# KammsensorV2.net
KiCad netlist of a schematic drawn in EAGLE
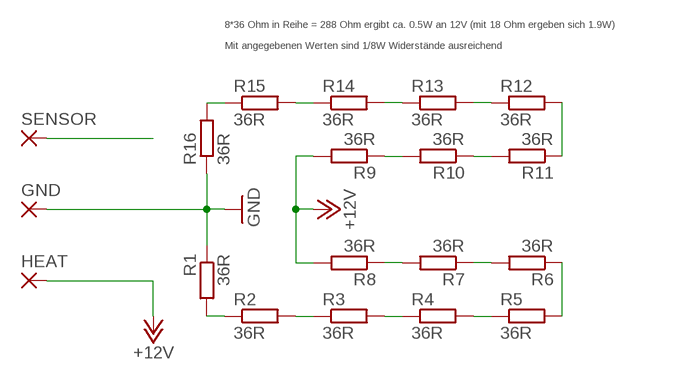
[diagram p0: schematic, sheet 1]

(export (version "E")
  (design (tool "Eeschema 10.0.6"))
  (components
    (comp (ref "GND")
      (value "WIREPADSMD5-1,8")
      (footprint "eagle-import:5-1,8")
      (libsource (lib "eagle-import") (part "WIREPADSMD5-1,8"))
    )
    (comp (ref "HEAT")
      (value "WIREPADSMD5-1,8")
      (footprint "eagle-import:5-1,8")
      (libsource (lib "eagle-import") (part "WIREPADSMD5-1,8"))
    )
    (comp (ref "R1")
      (value "36R")
      (footprint "eagle-import:M1206")
      (libsource (lib "eagle-import") (part "R-EU_M1206"))
    )
    (comp (ref "R2")
      (value "36R")
      (footprint "eagle-import:M1206")
      (libsource (lib "eagle-import") (part "R-EU_M1206"))
    )
    (comp (ref "R3")
      (value "36R")
      (footprint "eagle-import:M1206")
      (libsource (lib "eagle-import") (part "R-EU_M1206"))
    )
    (comp (ref "R4")
      (value "36R")
      (footprint "eagle-import:M1206")
      (libsource (lib "eagle-import") (part "R-EU_M1206"))
    )
    (comp (ref "R5")
      (value "36R")
      (footprint "eagle-import:M1206")
      (libsource (lib "eagle-import") (part "R-EU_M1206"))
    )
    (comp (ref "R6")
      (value "36R")
      (footprint "eagle-import:M1206")
      (libsource (lib "eagle-import") (part "R-EU_M1206"))
    )
    (comp (ref "R7")
      (value "36R")
      (footprint "eagle-import:M1206")
      (libsource (lib "eagle-import") (part "R-EU_M1206"))
    )
    (comp (ref "R8")
      (value "36R")
      (footprint "eagle-import:M1206")
      (libsource (lib "eagle-import") (part "R-EU_M1206"))
    )
    (comp (ref "R9")
      (value "36R")
      (footprint "eagle-import:M1206")
      (libsource (lib "eagle-import") (part "R-EU_M1206"))
    )
    (comp (ref "R10")
      (value "36R")
      (footprint "eagle-import:M1206")
      (libsource (lib "eagle-import") (part "R-EU_M1206"))
    )
    (comp (ref "R11")
      (value "36R")
      (footprint "eagle-import:M1206")
      (libsource (lib "eagle-import") (part "R-EU_M1206"))
    )
    (comp (ref "R12")
      (value "36R")
      (footprint "eagle-import:M1206")
      (libsource (lib "eagle-import") (part "R-EU_M1206"))
    )
    (comp (ref "R13")
      (value "36R")
      (footprint "eagle-import:M1206")
      (libsource (lib "eagle-import") (part "R-EU_M1206"))
    )
    (comp (ref "R14")
      (value "36R")
      (footprint "eagle-import:M1206")
      (libsource (lib "eagle-import") (part "R-EU_M1206"))
    )
    (comp (ref "R15")
      (value "36R")
      (footprint "eagle-import:M1206")
      (libsource (lib "eagle-import") (part "R-EU_M1206"))
    )
    (comp (ref "R16")
      (value "36R")
      (footprint "eagle-import:M1206")
      (libsource (lib "eagle-import") (part "R-EU_M1206"))
    )
    (comp (ref "SENSOR")
      (value "WIREPADSMD5-1,8")
      (footprint "eagle-import:5-1,8")
      (libsource (lib "eagle-import") (part "WIREPADSMD5-1,8"))
    )
  )
  (nets
    (net (code "1") (name "+12V") (class "Default")
      (node (ref "HEAT") (pin "1") (pinfunction "P_1") (pintype "passive"))
      (node (ref "R8") (pin "2") (pinfunction "2_2") (pintype "passive"))
      (node (ref "R9") (pin "2") (pinfunction "2_2") (pintype "passive"))
    )
    (net (code "2") (name "GND") (class "Default")
      (node (ref "GND") (pin "1") (pinfunction "P_1") (pintype "passive"))
      (node (ref "R1") (pin "1") (pinfunction "1_1") (pintype "passive"))
      (node (ref "R16") (pin "1") (pinfunction "1_1") (pintype "passive"))
    )
    (net (code "3") (name "Net-(R1-Pad2)") (class "Default")
      (node (ref "R1") (pin "2") (pinfunction "2_2") (pintype "passive"))
      (node (ref "R2") (pin "1") (pinfunction "1_1") (pintype "passive"))
    )
    (net (code "4") (name "Net-(R2-Pad2)") (class "Default")
      (node (ref "R2") (pin "2") (pinfunction "2_2") (pintype "passive"))
      (node (ref "R3") (pin "1") (pinfunction "1_1") (pintype "passive"))
    )
    (net (code "5") (name "Net-(R3-Pad2)") (class "Default")
      (node (ref "R3") (pin "2") (pinfunction "2_2") (pintype "passive"))
      (node (ref "R4") (pin "1") (pinfunction "1_1") (pintype "passive"))
    )
    (net (code "6") (name "Net-(R4-Pad2)") (class "Default")
      (node (ref "R4") (pin "2") (pinfunction "2_2") (pintype "passive"))
      (node (ref "R5") (pin "1") (pinfunction "1_1") (pintype "passive"))
    )
    (net (code "7") (name "Net-(R5-Pad2)") (class "Default")
      (node (ref "R5") (pin "2") (pinfunction "2_2") (pintype "passive"))
      (node (ref "R6") (pin "1") (pinfunction "1_1") (pintype "passive"))
    )
    (net (code "8") (name "Net-(R6-Pad2)") (class "Default")
      (node (ref "R6") (pin "2") (pinfunction "2_2") (pintype "passive"))
      (node (ref "R7") (pin "1") (pinfunction "1_1") (pintype "passive"))
    )
    (net (code "9") (name "Net-(R7-Pad2)") (class "Default")
      (node (ref "R7") (pin "2") (pinfunction "2_2") (pintype "passive"))
      (node (ref "R8") (pin "1") (pinfunction "1_1") (pintype "passive"))
    )
    (net (code "10") (name "Net-(R10-Pad1)") (class "Default")
      (node (ref "R10") (pin "1") (pinfunction "1_1") (pintype "passive"))
      (node (ref "R11") (pin "2") (pinfunction "2_2") (pintype "passive"))
    )
    (net (code "11") (name "Net-(R10-Pad2)") (class "Default")
      (node (ref "R10") (pin "2") (pinfunction "2_2") (pintype "passive"))
      (node (ref "R9") (pin "1") (pinfunction "1_1") (pintype "passive"))
    )
    (net (code "12") (name "Net-(R11-Pad1)") (class "Default")
      (node (ref "R11") (pin "1") (pinfunction "1_1") (pintype "passive"))
      (node (ref "R12") (pin "2") (pinfunction "2_2") (pintype "passive"))
    )
    (net (code "13") (name "Net-(R12-Pad1)") (class "Default")
      (node (ref "R12") (pin "1") (pinfunction "1_1") (pintype "passive"))
      (node (ref "R13") (pin "2") (pinfunction "2_2") (pintype "passive"))
    )
    (net (code "14") (name "Net-(R13-Pad1)") (class "Default")
      (node (ref "R13") (pin "1") (pinfunction "1_1") (pintype "passive"))
      (node (ref "R14") (pin "2") (pinfunction "2_2") (pintype "passive"))
    )
    (net (code "15") (name "Net-(R14-Pad1)") (class "Default")
      (node (ref "R14") (pin "1") (pinfunction "1_1") (pintype "passive"))
      (node (ref "R15") (pin "2") (pinfunction "2_2") (pintype "passive"))
    )
    (net (code "16") (name "Net-(R15-Pad1)") (class "Default")
      (node (ref "R15") (pin "1") (pinfunction "1_1") (pintype "passive"))
      (node (ref "R16") (pin "2") (pinfunction "2_2") (pintype "passive"))
    )
    (net (code "17") (name "unconnected-(SENSOR-P-Pad1)") (class "Default")
      (node (ref "SENSOR") (pin "1") (pinfunction "P_1") (pintype "passive"))
    )
  )
)
